# sfp-experimenter.net
KiCad netlist of a schematic drawn in EAGLE
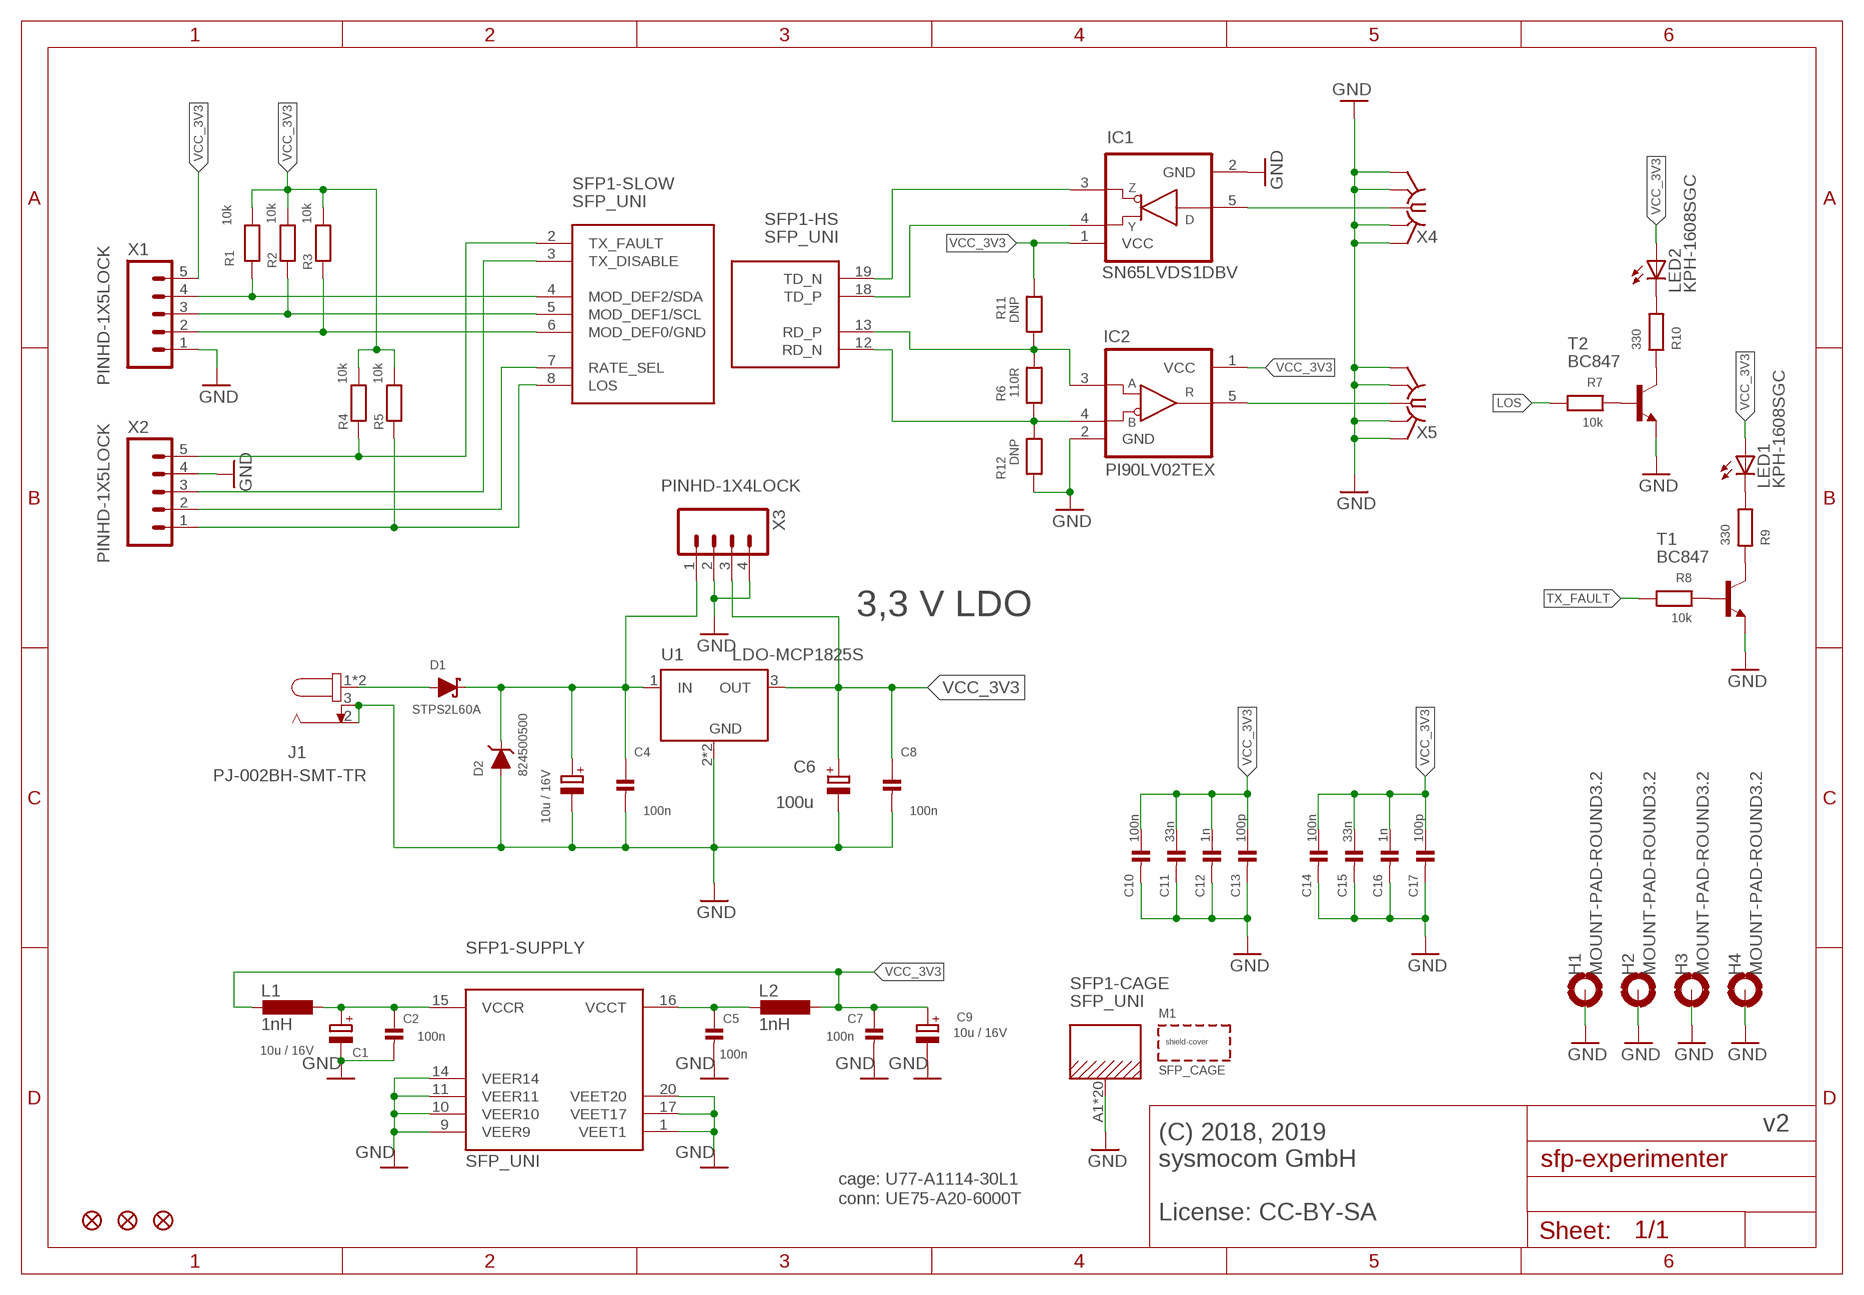
[diagram p0: schematic, sheet 1]

(export (version "E")
  (design (tool "Eeschema 10.0.6"))
  (components
    (comp (ref "C1")
      (value "10u / 16V")
      (footprint "eagle-import:CPOL1206")
      (description "CAP CER 10UF 16V X5R 1206")
      (fields
        (field (name "MANUFACTURER") "Samsung Electro-Mechanics")
        (field (name "MANUFACTURERPARTNUMBER") "CL31A106KOHNNNE")
      )
      (libsource (lib "eagle-import") (part "CPOL-EU-1206"))
    )
    (comp (ref "C2")
      (value "100n")
      (footprint "eagle-import:_0603")
      (description "CAP CER 0.1UF 16V X7R 0603")
      (fields
        (field (name "MANUFACTURER") "Samsung Electro-Mechanics")
        (field (name "MANUFACTURERPARTNUMBER") "CL10B104KO8NNNC")
      )
      (libsource (lib "eagle-import") (part "CAP_CERAMIC_0603"))
    )
    (comp (ref "C3")
      (value "10u / 16V")
      (footprint "eagle-import:CPOL1206")
      (description "CAP CER 10UF 16V X5R 1206")
      (fields
        (field (name "MANUFACTURER") "Samsung Electro-Mechanics")
        (field (name "MANUFACTURERPARTNUMBER") "CL31A106KOHNNNE")
      )
      (libsource (lib "eagle-import") (part "CPOL-EU-1206"))
    )
    (comp (ref "C4")
      (value "100n")
      (footprint "eagle-import:_0603")
      (description "CAP CER 0.1UF 16V X7R 0603")
      (fields
        (field (name "MANUFACTURER") "Samsung Electro-Mechanics")
        (field (name "MANUFACTURERPARTNUMBER") "CL10B104KO8NNNC")
      )
      (libsource (lib "eagle-import") (part "CAP_CERAMIC_0603"))
    )
    (comp (ref "C5")
      (value "100n")
      (footprint "eagle-import:_0603")
      (description "CAP CER 0.1UF 16V X7R 0603")
      (fields
        (field (name "MANUFACTURER") "Samsung Electro-Mechanics")
        (field (name "MANUFACTURERPARTNUMBER") "CL10B104KO8NNNC")
      )
      (libsource (lib "eagle-import") (part "CAP_CERAMIC_0603"))
    )
    (comp (ref "C6")
      (value "100u")
      (footprint "eagle-import:CT6032")
      (description "CAP TANT POLY 100UF 6.3V 2312")
      (fields
        (field (name "MANUFACTURER") "KEMET")
        (field (name "MANUFACTURERPARTNUMBER") "T520C107M006ATE045")
      )
      (libsource (lib "eagle-import") (part "CPOL-EUCT6032"))
    )
    (comp (ref "C7")
      (value "100n")
      (footprint "eagle-import:_0603")
      (description "CAP CER 0.1UF 16V X7R 0603")
      (fields
        (field (name "MANUFACTURER") "Samsung Electro-Mechanics")
        (field (name "MANUFACTURERPARTNUMBER") "CL10B104KO8NNNC")
      )
      (libsource (lib "eagle-import") (part "CAP_CERAMIC_0603"))
    )
    (comp (ref "C8")
      (value "100n")
      (footprint "eagle-import:_0603")
      (description "CAP CER 0.1UF 16V X7R 0603")
      (fields
        (field (name "MANUFACTURER") "Samsung Electro-Mechanics")
        (field (name "MANUFACTURERPARTNUMBER") "CL10B104KO8NNNC")
      )
      (libsource (lib "eagle-import") (part "CAP_CERAMIC_0603"))
    )
    (comp (ref "C9")
      (value "10u / 16V")
      (footprint "eagle-import:CPOL1206")
      (description "CAP CER 10UF 16V X5R 1206")
      (fields
        (field (name "MANUFACTURER") "Samsung Electro-Mechanics")
        (field (name "MANUFACTURERPARTNUMBER") "CL31A106KOHNNNE")
      )
      (libsource (lib "eagle-import") (part "CPOL-EU-1206"))
    )
    (comp (ref "C10")
      (value "100n")
      (footprint "eagle-import:_0603")
      (description "CAP CER 0.1UF 16V X7R 0603")
      (fields
        (field (name "MANUFACTURER") "Samsung Electro-Mechanics")
        (field (name "MANUFACTURERPARTNUMBER") "CL10B104KO8NNNC")
      )
      (libsource (lib "eagle-import") (part "CAP_CERAMIC_0603"))
    )
    (comp (ref "C11")
      (value "33n")
      (footprint "eagle-import:_0603")
      (description "CAP CER 0.033UF 50V X7R 0603")
      (fields
        (field (name "MANUFACTURER") "AVX Corporation")
        (field (name "MANUFACTURERPARTNUMBER") "06035C333JAT2A")
      )
      (libsource (lib "eagle-import") (part "CAP_CERAMIC_0603"))
    )
    (comp (ref "C12")
      (value "1n")
      (footprint "eagle-import:_0603")
      (description "CAP CER 1000PF 50V X7R 0603")
      (fields
        (field (name "MANUFACTURER") "Yageo")
        (field (name "MANUFACTURERPARTNUMBER") "CC0603KRX7R9BB102")
      )
      (libsource (lib "eagle-import") (part "CAP_CERAMIC_0603"))
    )
    (comp (ref "C13")
      (value "100p")
      (footprint "eagle-import:_0603")
      (description "CAP CER 100PF 50V C0G/NPO 0603")
      (fields
        (field (name "MANUFACTURER") "Yageo")
        (field (name "MANUFACTURERPARTNUMBER") "CC0603JRNPO9BN101")
      )
      (libsource (lib "eagle-import") (part "CAP_CERAMIC_0603"))
    )
    (comp (ref "C14")
      (value "100n")
      (footprint "eagle-import:_0603")
      (description "CAP CER 0.1UF 16V X7R 0603")
      (fields
        (field (name "MANUFACTURER") "Samsung Electro-Mechanics")
        (field (name "MANUFACTURERPARTNUMBER") "CL10B104KO8NNNC")
      )
      (libsource (lib "eagle-import") (part "CAP_CERAMIC_0603"))
    )
    (comp (ref "C15")
      (value "33n")
      (footprint "eagle-import:_0603")
      (description "CAP CER 0.033UF 50V X7R 0603")
      (fields
        (field (name "MANUFACTURER") "AVX Corporation")
        (field (name "MANUFACTURERPARTNUMBER") "06035C333JAT2A")
      )
      (libsource (lib "eagle-import") (part "CAP_CERAMIC_0603"))
    )
    (comp (ref "C16")
      (value "1n")
      (footprint "eagle-import:_0603")
      (description "CAP CER 1000PF 50V X7R 0603")
      (fields
        (field (name "MANUFACTURER") "Yageo")
        (field (name "MANUFACTURERPARTNUMBER") "CC0603KRX7R9BB102")
      )
      (libsource (lib "eagle-import") (part "CAP_CERAMIC_0603"))
    )
    (comp (ref "C17")
      (value "100p")
      (footprint "eagle-import:_0603")
      (description "CAP CER 100PF 50V C0G/NPO 0603")
      (fields
        (field (name "MANUFACTURER") "Yageo")
        (field (name "MANUFACTURERPARTNUMBER") "CC0603JRNPO9BN101")
      )
      (libsource (lib "eagle-import") (part "CAP_CERAMIC_0603"))
    )
    (comp (ref "D1")
      (value "STPS2L60A")
      (footprint "eagle-import:SMADIODE")
      (description "DIODE SCHOTTKY 60V 2A SMA")
      (fields (field (name "MANUFACTURER") "STMicroelectronics"))
      (libsource (lib "eagle-import") (part "DIODE-SCHOTTKY-SMA"))
    )
    (comp (ref "D2")
      (value "824500500")
      (footprint "eagle-import:SMADIODE")
      (description "TVS DIODE 5VWM 9.2VC SMA")
      (fields (field (name "MANUFACTURER") "Bourns Inc.") (field (name "MANUFACTURERPARTNUMBER") "SMAJ5.0A"))
      (libsource (lib "eagle-import") (part "DIODE-TVS-SMA"))
    )
    (comp (ref "FID1")
      (value "FIDUCIAL1X2.5")
      (footprint "eagle-import:FIDUCIAL-1X2.5")
      (libsource (lib "eagle-import") (part "FIDUCIAL1X2.5"))
    )
    (comp (ref "FID2")
      (value "FIDUCIAL1X2.5")
      (footprint "eagle-import:FIDUCIAL-1X2.5")
      (libsource (lib "eagle-import") (part "FIDUCIAL1X2.5"))
    )
    (comp (ref "FID3")
      (value "FIDUCIAL1X2.5")
      (footprint "eagle-import:FIDUCIAL-1X2.5")
      (libsource (lib "eagle-import") (part "FIDUCIAL1X2.5"))
    )
    (comp (ref "H1")
      (value "MOUNT-PAD-ROUND3.2")
      (footprint "eagle-import:3,2-PAD")
      (description "NO DESCRIPTION")
      (fields
        (field (name "MANUFACTURER") "UNKNOWN MANUFACTURER")
        (field (name "MANUFACTURERPARTNUMBER") "UNKNOWN MANUFACTURER PART NUMBER")
      )
      (libsource (lib "eagle-import") (part "MOUNT-PAD-ROUND3.2"))
    )
    (comp (ref "H2")
      (value "MOUNT-PAD-ROUND3.2")
      (footprint "eagle-import:3,2-PAD")
      (description "NO DESCRIPTION")
      (fields
        (field (name "MANUFACTURER") "UNKNOWN MANUFACTURER")
        (field (name "MANUFACTURERPARTNUMBER") "UNKNOWN MANUFACTURER PART NUMBER")
      )
      (libsource (lib "eagle-import") (part "MOUNT-PAD-ROUND3.2"))
    )
    (comp (ref "H3")
      (value "MOUNT-PAD-ROUND3.2")
      (footprint "eagle-import:3,2-PAD")
      (description "NO DESCRIPTION")
      (fields
        (field (name "MANUFACTURER") "UNKNOWN MANUFACTURER")
        (field (name "MANUFACTURERPARTNUMBER") "UNKNOWN MANUFACTURER PART NUMBER")
      )
      (libsource (lib "eagle-import") (part "MOUNT-PAD-ROUND3.2"))
    )
    (comp (ref "H4")
      (value "MOUNT-PAD-ROUND3.2")
      (footprint "eagle-import:3,2-PAD")
      (description "NO DESCRIPTION")
      (fields
        (field (name "MANUFACTURER") "UNKNOWN MANUFACTURER")
        (field (name "MANUFACTURERPARTNUMBER") "UNKNOWN MANUFACTURER PART NUMBER")
      )
      (libsource (lib "eagle-import") (part "MOUNT-PAD-ROUND3.2"))
    )
    (comp (ref "IC1")
      (value "SN65LVDS1DBV")
      (footprint "eagle-import:SOT23-5")
      (description "IC DRIVER 1/0 SOT23-5")
      (fields
        (field (name "MANUFACTURER") "Texas Instruments")
        (field (name "MANUFACTURERPARTNUMBER") "SN65LVDS1DBVR")
      )
      (libsource (lib "eagle-import") (part "SN65LVDS1DBV"))
    )
    (comp (ref "IC2")
      (value "PI90LV02TEX")
      (footprint "eagle-import:SOT23-5")
      (description "IC RECEIVER 0/1 SOT23-5")
      (fields (field (name "MANUFACTURER") "Diodes Incorporated"))
      (libsource (lib "eagle-import") (part "SN65LVDT2DBV"))
    )
    (comp (ref "J1")
      (value "PJ-002BH-SMT-TR")
      (footprint "eagle-import:694108106102")
      (description "CONN PWR JACK 2.5X5.5MM SOLDER")
      (fields (field (name "MANUFACTURER") "CUI Devices"))
      (libsource (lib "eagle-import") (part "694108106102"))
    )
    (comp (ref "L1")
      (value "1nH")
      (footprint "eagle-import:0603")
      (description "FIXED IND 1NH 500MA 50 MOHM SMD")
      (fields
        (field (name "MANUFACTURER") "Abracon LLC")
        (field (name "MANUFACTURERPARTNUMBER") "AIMC-0603-1N0S-T")
      )
      (libsource (lib "eagle-import") (part "L-EU_0603"))
    )
    (comp (ref "L2")
      (value "1nH")
      (footprint "eagle-import:0603")
      (description "FIXED IND 1NH 500MA 50 MOHM SMD")
      (fields
        (field (name "MANUFACTURER") "Abracon LLC")
        (field (name "MANUFACTURERPARTNUMBER") "AIMC-0603-1N0S-T")
      )
      (libsource (lib "eagle-import") (part "L-EU_0603"))
    )
    (comp (ref "LED1")
      (value "KPH-1608SGC")
      (footprint "eagle-import:CHIP-LED0603")
      (description "NO DESCRIPTION")
      (fields
        (field (name "MANUFACTURER") "UNKNOWN MANUFACTURER")
        (field (name "MANUFACTURERPARTNUMBER") "UNKNOWN MANUFACTURER PART NUMBER")
      )
      (libsource (lib "eagle-import") (part "LEDCHIP-LED0603"))
    )
    (comp (ref "LED2")
      (value "KPH-1608SGC")
      (footprint "eagle-import:CHIP-LED0603")
      (description "NO DESCRIPTION")
      (fields
        (field (name "MANUFACTURER") "UNKNOWN MANUFACTURER")
        (field (name "MANUFACTURERPARTNUMBER") "UNKNOWN MANUFACTURER PART NUMBER")
      )
      (libsource (lib "eagle-import") (part "LEDCHIP-LED0603"))
    )
    (comp (ref "R1")
      (value "10k")
      (footprint "eagle-import:_0603")
      (description "RES 10K OHM 1% 1/10W 0603")
      (fields (field (name "MANUFACTURER") "YAGEO") (field (name "MANUFACTURERPARTNUMBER") "RC0603FR-0710KL"))
      (libsource (lib "eagle-import") (part "sfp-experimenter_RESISTOR_0603"))
    )
    (comp (ref "R2")
      (value "10k")
      (footprint "eagle-import:_0603")
      (description "RES 10K OHM 1% 1/10W 0603")
      (fields (field (name "MANUFACTURER") "YAGEO") (field (name "MANUFACTURERPARTNUMBER") "RC0603FR-0710KL"))
      (libsource (lib "eagle-import") (part "sfp-experimenter_RESISTOR_0603"))
    )
    (comp (ref "R3")
      (value "10k")
      (footprint "eagle-import:_0603")
      (description "RES 10K OHM 1% 1/10W 0603")
      (fields (field (name "MANUFACTURER") "YAGEO") (field (name "MANUFACTURERPARTNUMBER") "RC0603FR-0710KL"))
      (libsource (lib "eagle-import") (part "sfp-experimenter_RESISTOR_0603"))
    )
    (comp (ref "R4")
      (value "10k")
      (footprint "eagle-import:_0603")
      (description "RES 10K OHM 1% 1/10W 0603")
      (fields (field (name "MANUFACTURER") "YAGEO") (field (name "MANUFACTURERPARTNUMBER") "RC0603FR-0710KL"))
      (libsource (lib "eagle-import") (part "sfp-experimenter_RESISTOR_0603"))
    )
    (comp (ref "R5")
      (value "10k")
      (footprint "eagle-import:_0603")
      (description "RES 10K OHM 1% 1/10W 0603")
      (fields (field (name "MANUFACTURER") "YAGEO") (field (name "MANUFACTURERPARTNUMBER") "RC0603FR-0710KL"))
      (libsource (lib "eagle-import") (part "sfp-experimenter_RESISTOR_0603"))
    )
    (comp (ref "R6")
      (value "110R")
      (footprint "eagle-import:_0402")
      (description "RES 110 OHM 1% 1/10W 0603")
      (fields
        (field (name "MANUFACTURER") "YAGEO")
        (field (name "MANUFACTURERPARTNUMBER") "RC0603FR-13110RL")
      )
      (libsource (lib "eagle-import") (part "sfp-experimenter_RESISTOR_0402"))
    )
    (comp (ref "R7")
      (value "10k")
      (footprint "eagle-import:_0603")
      (description "RES 10K OHM 1% 1/10W 0603")
      (fields (field (name "MANUFACTURER") "YAGEO") (field (name "MANUFACTURERPARTNUMBER") "RC0603FR-0710KL"))
      (libsource (lib "eagle-import") (part "RESISTOR_0603"))
    )
    (comp (ref "R8")
      (value "10k")
      (footprint "eagle-import:_0603")
      (description "RES 10K OHM 1% 1/10W 0603")
      (fields (field (name "MANUFACTURER") "YAGEO") (field (name "MANUFACTURERPARTNUMBER") "RC0603FR-0710KL"))
      (libsource (lib "eagle-import") (part "RESISTOR_0603"))
    )
    (comp (ref "R9")
      (value "330")
      (footprint "eagle-import:_0603")
      (description "RES SMD 330 OHM 5% 1/10W 0603")
      (fields
        (field (name "MANUFACTURER") "Panasonic Electronic Components")
        (field (name "MANUFACTURERPARTNUMBER") "ERJ-3GEYJ331V")
      )
      (libsource (lib "eagle-import") (part "RESISTOR_0603"))
    )
    (comp (ref "R10")
      (value "330")
      (footprint "eagle-import:_0603")
      (description "RES SMD 330 OHM 5% 1/10W 0603")
      (fields
        (field (name "MANUFACTURER") "Panasonic Electronic Components")
        (field (name "MANUFACTURERPARTNUMBER") "ERJ-3GEYJ331V")
      )
      (libsource (lib "eagle-import") (part "RESISTOR_0603"))
    )
    (comp (ref "R11")
      (value "DNP")
      (footprint "eagle-import:_0603")
      (description "NO DESCRIPTION")
      (fields
        (field (name "MANUFACTURER") "UNKNOWN MANUFACTURER")
        (field (name "MANUFACTURERPARTNUMBER") "UNKNOWN MANUFACTURER PART NUMBER")
      )
      (libsource (lib "eagle-import") (part "sfp-experimenter_RESISTOR_0603"))
    )
    (comp (ref "R12")
      (value "DNP")
      (footprint "eagle-import:_0603")
      (description "RES 100K OHM 1% 1/10W 0603")
      (fields
        (field (name "MANUFACTURER") "KOA Speer Electronics, Inc.")
        (field (name "MANUFACTURERPARTNUMBER") "RK73H1JTTD1003F")
      )
      (libsource (lib "eagle-import") (part "RESISTOR_0603"))
    )
    (comp (ref "SFP1")
      (value "SFP_UNI")
      (footprint "eagle-import:SFP_COMBINED")
      (description "CONN SFP RCPT 20POS SLD R/A SMD")
      (fields
        (field (name "CLASS") "SFP")
        (field (name "LINK") "https://www.digikey.com/product-detail/en/amphenol-icc-commercial-products/UE75-A20-6000T/UE75-A20-6000TCT-ND/1242798")
        (field (name "MANUFACTURER") "Amphenol ICC (Commercial Products)")
        (field (name "MANUFACTURERPARTNUMBER") "UE75-A20-6000T")
        (field (name "POPULATED") "TRUE")
        (field (name "ROHSCERTIFICATE") "RoHS Compliant")
        (field (name "SOURCE") "DIGIKEY")
        (field (name "SOURCEPARTNUMBER") "UE75-A20-6000TCT-ND")
      )
      (libsource (lib "eagle-import") (part "SFP_UNI"))
    )
    (comp (ref "T1")
      (value "BC847")
      (footprint "eagle-import:SOT23-BEC")
      (description "TRANS NPN GP 100MA 45V SOT23")
      (fields
        (field (name "MANUFACTURER") "NXP Semiconductors")
        (field (name "MANUFACTURERPARTNUMBER") "BC847C,215")
      )
      (libsource (lib "eagle-import") (part "-NPN-SOT23-BECBC847C"))
    )
    (comp (ref "T2")
      (value "BC847")
      (footprint "eagle-import:SOT23-BEC")
      (description "TRANS NPN GP 100MA 45V SOT23")
      (fields
        (field (name "MANUFACTURER") "NXP Semiconductors")
        (field (name "MANUFACTURERPARTNUMBER") "BC847C,215")
      )
      (libsource (lib "eagle-import") (part "-NPN-SOT23-BECBC847C"))
    )
    (comp (ref "U1")
      (value "LDO-MCP1825S")
      (footprint "eagle-import:SOT223")
      (description "IC REG LIN 3.3V 500MA SOT223-3")
      (fields
        (field (name "MANUFACTURER") "Microchip Technology")
        (field (name "MANUFACTURERPARTNUMBER") "MCP1825ST-3302E/DB")
      )
      (libsource (lib "eagle-import") (part "LDO-MCP1825S"))
    )
    (comp (ref "X1")
      (value "PINHD-1X5LOCK")
      (footprint "eagle-import:1X05_LOCK")
      (description "NO DESCRIPTION")
      (fields
        (field (name "MANUFACTURER") "UNKNOWN MANUFACTURER")
        (field (name "MANUFACTURERPARTNUMBER") "UNKNOWN MANUFACTURER PART NUMBER")
      )
      (libsource (lib "eagle-import") (part "PINHD-1X5LOCK"))
    )
    (comp (ref "X2")
      (value "PINHD-1X5LOCK")
      (footprint "eagle-import:1X05_LOCK")
      (description "NO DESCRIPTION")
      (fields
        (field (name "MANUFACTURER") "UNKNOWN MANUFACTURER")
        (field (name "MANUFACTURERPARTNUMBER") "UNKNOWN MANUFACTURER PART NUMBER")
      )
      (libsource (lib "eagle-import") (part "PINHD-1X5LOCK"))
    )
    (comp (ref "X3")
      (value "PINHD-1X4LOCK")
      (footprint "eagle-import:1X04_LOCK")
      (description "NO DESCRIPTION")
      (fields
        (field (name "MANUFACTURER") "UNKNOWN MANUFACTURER")
        (field (name "MANUFACTURERPARTNUMBER") "UNKNOWN MANUFACTURER PART NUMBER")
      )
      (libsource (lib "eagle-import") (part "PINHD-1X4LOCK"))
    )
    (comp (ref "X4")
      (value "SMA-F-S-EDGE")
      (footprint "eagle-import:SMA-F-S-EDGE")
      (description "NO DESCRIPTION")
      (fields
        (field (name "MANUFACTURER") "UNKNOWN MANUFACTURER")
        (field (name "MANUFACTURERPARTNUMBER") "UNKNOWN MANUFACTURER PART NUMBER")
      )
      (libsource (lib "eagle-import") (part "SMA-F-S-EDGE"))
    )
    (comp (ref "X5")
      (value "SMA-F-S-EDGE")
      (footprint "eagle-import:SMA-F-S-EDGE")
      (description "NO DESCRIPTION")
      (fields
        (field (name "MANUFACTURER") "UNKNOWN MANUFACTURER")
        (field (name "MANUFACTURERPARTNUMBER") "UNKNOWN MANUFACTURER PART NUMBER")
      )
      (libsource (lib "eagle-import") (part "SMA-F-S-EDGE"))
    )
  )
  (nets
    (net (code "1") (name "GND") (class "Default")
      (node (ref "C1") (pin "-") (pinfunction "-_-") (pintype "passive"))
      (node (ref "C10") (pin "2") (pinfunction "2_2") (pintype "passive"))
      (node (ref "C11") (pin "2") (pinfunction "2_2") (pintype "passive"))
      (node (ref "C12") (pin "2") (pinfunction "2_2") (pintype "passive"))
      (node (ref "C13") (pin "2") (pinfunction "2_2") (pintype "passive"))
      (node (ref "C14") (pin "2") (pinfunction "2_2") (pintype "passive"))
      (node (ref "C15") (pin "2") (pinfunction "2_2") (pintype "passive"))
      (node (ref "C16") (pin "2") (pinfunction "2_2") (pintype "passive"))
      (node (ref "C17") (pin "2") (pinfunction "2_2") (pintype "passive"))
      (node (ref "C2") (pin "2") (pinfunction "2_2") (pintype "passive"))
      (node (ref "C3") (pin "-") (pinfunction "-_-") (pintype "passive"))
      (node (ref "C4") (pin "2") (pinfunction "2_2") (pintype "passive"))
      (node (ref "C5") (pin "2") (pinfunction "2_2") (pintype "passive"))
      (node (ref "C6") (pin "-") (pinfunction "-_-") (pintype "passive"))
      (node (ref "C7") (pin "2") (pinfunction "2_2") (pintype "passive"))
      (node (ref "C8") (pin "2") (pinfunction "2_2") (pintype "passive"))
      (node (ref "C9") (pin "-") (pinfunction "-_-") (pintype "passive"))
      (node (ref "D2") (pin "A") (pinfunction "A_A") (pintype "passive"))
      (node (ref "H1") (pin "B3,2") (pinfunction "MOUNT_B3,2") (pintype "passive"))
      (node (ref "H2") (pin "B3,2") (pinfunction "MOUNT_B3,2") (pintype "passive"))
      (node (ref "H3") (pin "B3,2") (pinfunction "MOUNT_B3,2") (pintype "passive"))
      (node (ref "H4") (pin "B3,2") (pinfunction "MOUNT_B3,2") (pintype "passive"))
      (node (ref "IC1") (pin "2") (pinfunction "GND_2") (pintype "power_in"))
      (node (ref "IC2") (pin "2") (pinfunction "GND_2") (pintype "power_in"))
      (node (ref "J1") (pin "2") (pinfunction "2_2") (pintype "passive"))
      (node (ref "J1") (pin "3") (pinfunction "3_3") (pintype "passive"))
      (node (ref "R12") (pin "2") (pinfunction "2_2") (pintype "passive"))
      (node (ref "SFP1") (pin "1") (pinfunction "VEET1_1") (pintype "power_in"))
      (node (ref "SFP1") (pin "10") (pinfunction "VEER10_10") (pintype "power_in"))
      (node (ref "SFP1") (pin "11") (pinfunction "VEER11_11") (pintype "power_in"))
      (node (ref "SFP1") (pin "14") (pinfunction "VEER14_14") (pintype "power_in"))
      (node (ref "SFP1") (pin "17") (pinfunction "VEET17_17") (pintype "power_in"))
      (node (ref "SFP1") (pin "20") (pinfunction "VEET20_20") (pintype "power_in"))
      (node (ref "SFP1") (pin "9") (pinfunction "VEER9_9") (pintype "power_in"))
      (node (ref "SFP1") (pin "A1") (pinfunction "CAGE_A1") (pintype "power_in"))
      (node (ref "SFP1") (pin "A10") (pinfunction "CAGE_A10") (pintype "power_in"))
      (node (ref "SFP1") (pin "A11") (pinfunction "CAGE_A11") (pintype "power_in"))
      (node (ref "SFP1") (pin "A12") (pinfunction "CAGE_A12") (pintype "power_in"))
      (node (ref "SFP1") (pin "A2") (pinfunction "CAGE_A2") (pintype "power_in"))
      (node (ref "SFP1") (pin "A3") (pinfunction "CAGE_A3") (pintype "power_in"))
      (node (ref "SFP1") (pin "A4") (pinfunction "CAGE_A4") (pintype "power_in"))
      (node (ref "SFP1") (pin "A5") (pinfunction "CAGE_A5") (pintype "power_in"))
      (node (ref "SFP1") (pin "A6") (pinfunction "CAGE_A6") (pintype "power_in"))
      (node (ref "SFP1") (pin "A7") (pinfunction "CAGE_A7") (pintype "power_in"))
      (node (ref "SFP1") (pin "A8") (pinfunction "CAGE_A8") (pintype "power_in"))
      (node (ref "SFP1") (pin "B1") (pinfunction "CAGE_B1") (pintype "power_in"))
      (node (ref "SFP1") (pin "B10") (pinfunction "CAGE_B10") (pintype "power_in"))
      (node (ref "SFP1") (pin "B2") (pinfunction "CAGE_B2") (pintype "power_in"))
      (node (ref "SFP1") (pin "B3") (pinfunction "CAGE_B3") (pintype "power_in"))
      (node (ref "SFP1") (pin "B4") (pinfunction "CAGE_B4") (pintype "power_in"))
      (node (ref "SFP1") (pin "B5") (pinfunction "CAGE_B5") (pintype "power_in"))
      (node (ref "SFP1") (pin "B6") (pinfunction "CAGE_B6") (pintype "power_in"))
      (node (ref "SFP1") (pin "B7") (pinfunction "CAGE_B7") (pintype "power_in"))
      (node (ref "SFP1") (pin "B8") (pinfunction "CAGE_B8") (pintype "power_in"))
      (node (ref "T1") (pin "E") (pinfunction "E_E") (pintype "passive"))
      (node (ref "T2") (pin "E") (pinfunction "E_E") (pintype "passive"))
      (node (ref "U1") (pin "2") (pinfunction "GND_2") (pintype "power_in"))
      (node (ref "U1") (pin "4") (pinfunction "GND_4") (pintype "power_in"))
      (node (ref "X1") (pin "1") (pinfunction "1_1") (pintype "passive"))
      (node (ref "X2") (pin "4") (pinfunction "4_4") (pintype "passive"))
      (node (ref "X3") (pin "2") (pinfunction "2_2") (pintype "passive"))
      (node (ref "X3") (pin "4") (pinfunction "4_4") (pintype "passive"))
      (node (ref "X4") (pin "BG1") (pinfunction "GND_BG1") (pintype "power_in"))
      (node (ref "X4") (pin "BG2") (pinfunction "GND_BG2") (pintype "power_in"))
      (node (ref "X4") (pin "TG1") (pinfunction "GND_TG1") (pintype "power_in"))
      (node (ref "X4") (pin "TG2") (pinfunction "GND_TG2") (pintype "power_in"))
      (node (ref "X5") (pin "BG1") (pinfunction "GND_BG1") (pintype "power_in"))
      (node (ref "X5") (pin "BG2") (pinfunction "GND_BG2") (pintype "power_in"))
      (node (ref "X5") (pin "TG1") (pinfunction "GND_TG1") (pintype "power_in"))
      (node (ref "X5") (pin "TG2") (pinfunction "GND_TG2") (pintype "power_in"))
    )
    (net (code "2") (name "LOS") (class "Default")
      (node (ref "R5") (pin "1") (pinfunction "1_1") (pintype "passive"))
      (node (ref "R7") (pin "2") (pinfunction "2_2") (pintype "passive"))
      (node (ref "SFP1") (pin "8") (pinfunction "LOS_8") (pintype "output"))
      (node (ref "X2") (pin "1") (pinfunction "1_1") (pintype "passive"))
    )
    (net (code "3") (name "Net-(D1-PadA)") (class "Default")
      (node (ref "D1") (pin "A") (pinfunction "A_A") (pintype "passive"))
      (node (ref "J1") (pin "1") (pinfunction "1_1") (pintype "passive"))
      (node (ref "J1") (pin "1-1") (pinfunction "1_1-1") (pintype "passive"))
    )
    (net (code "4") (name "Net-(IC1-D)") (class "Default")
      (node (ref "IC1") (pin "5") (pinfunction "D_5") (pintype "input"))
      (node (ref "X4") (pin "C") (pinfunction "1_C") (pintype "passive"))
    )
    (net (code "5") (name "Net-(IC1-Y)") (class "Default")
      (node (ref "IC1") (pin "4") (pinfunction "Y_4") (pintype "output"))
      (node (ref "SFP1") (pin "18") (pinfunction "TD_P_18") (pintype "input"))
    )
    (net (code "6") (name "Net-(IC1-Z)") (class "Default")
      (node (ref "IC1") (pin "3") (pinfunction "Z_3") (pintype "output"))
      (node (ref "SFP1") (pin "19") (pinfunction "TD_N_19") (pintype "input"))
    )
    (net (code "7") (name "Net-(IC2-A)") (class "Default")
      (node (ref "IC2") (pin "3") (pinfunction "A_3") (pintype "input"))
      (node (ref "R11") (pin "2") (pinfunction "2_2") (pintype "passive"))
      (node (ref "R6") (pin "1") (pinfunction "1_1") (pintype "passive"))
      (node (ref "SFP1") (pin "13") (pinfunction "RD_P_13") (pintype "output"))
    )
    (net (code "8") (name "Net-(IC2-B)") (class "Default")
      (node (ref "IC2") (pin "4") (pinfunction "B_4") (pintype "input"))
      (node (ref "R12") (pin "1") (pinfunction "1_1") (pintype "passive"))
      (node (ref "R6") (pin "2") (pinfunction "2_2") (pintype "passive"))
      (node (ref "SFP1") (pin "12") (pinfunction "RD_N_12") (pintype "output"))
    )
    (net (code "9") (name "Net-(IC2-R)") (class "Default")
      (node (ref "IC2") (pin "5") (pinfunction "R_5") (pintype "output"))
      (node (ref "X5") (pin "C") (pinfunction "1_C") (pintype "passive"))
    )
    (net (code "10") (name "Net-(LED1-PadC)") (class "Default")
      (node (ref "LED1") (pin "C") (pinfunction "C_C") (pintype "passive"))
      (node (ref "R9") (pin "2") (pinfunction "2_2") (pintype "passive"))
    )
    (net (code "11") (name "Net-(LED2-PadC)") (class "Default")
      (node (ref "LED2") (pin "C") (pinfunction "C_C") (pintype "passive"))
      (node (ref "R10") (pin "2") (pinfunction "2_2") (pintype "passive"))
    )
    (net (code "12") (name "Net-(R7-Pad1)") (class "Default")
      (node (ref "R7") (pin "1") (pinfunction "1_1") (pintype "passive"))
      (node (ref "T2") (pin "B") (pinfunction "B_B") (pintype "passive"))
    )
    (net (code "13") (name "Net-(R8-Pad1)") (class "Default")
      (node (ref "R8") (pin "1") (pinfunction "1_1") (pintype "passive"))
      (node (ref "T1") (pin "B") (pinfunction "B_B") (pintype "passive"))
    )
    (net (code "14") (name "Net-(R9-Pad1)") (class "Default")
      (node (ref "R9") (pin "1") (pinfunction "1_1") (pintype "passive"))
      (node (ref "T1") (pin "C") (pinfunction "C_C") (pintype "passive"))
    )
    (net (code "15") (name "Net-(R10-Pad1)") (class "Default")
      (node (ref "R10") (pin "1") (pinfunction "1_1") (pintype "passive"))
      (node (ref "T2") (pin "C") (pinfunction "C_C") (pintype "passive"))
    )
    (net (code "16") (name "Net-(SFP1C-MOD_DEF0{slash}GND)") (class "Default")
      (node (ref "R3") (pin "1") (pinfunction "1_1") (pintype "passive"))
      (node (ref "SFP1") (pin "6") (pinfunction "MOD_DEF0/GND_6") (pintype "passive"))
      (node (ref "X1") (pin "2") (pinfunction "2_2") (pintype "passive"))
    )
    (net (code "17") (name "Net-(SFP1C-MOD_DEF1{slash}SCL)") (class "Default")
      (node (ref "R2") (pin "1") (pinfunction "1_1") (pintype "passive"))
      (node (ref "SFP1") (pin "5") (pinfunction "MOD_DEF1/SCL_5") (pintype "bidirectional"))
      (node (ref "X1") (pin "3") (pinfunction "3_3") (pintype "passive"))
    )
    (net (code "18") (name "Net-(SFP1C-MOD_DEF2{slash}SDA)") (class "Default")
      (node (ref "R1") (pin "1") (pinfunction "1_1") (pintype "passive"))
      (node (ref "SFP1") (pin "4") (pinfunction "MOD_DEF2/SDA_4") (pintype "bidirectional"))
      (node (ref "X1") (pin "4") (pinfunction "4_4") (pintype "passive"))
    )
    (net (code "19") (name "Net-(SFP1C-RATE_SEL)") (class "Default")
      (node (ref "SFP1") (pin "7") (pinfunction "RATE_SEL_7") (pintype "input"))
      (node (ref "X2") (pin "2") (pinfunction "2_2") (pintype "passive"))
    )
    (net (code "20") (name "Net-(SFP1C-TX_DISABLE)") (class "Default")
      (node (ref "SFP1") (pin "3") (pinfunction "TX_DISABLE_3") (pintype "input"))
      (node (ref "X2") (pin "3") (pinfunction "3_3") (pintype "passive"))
    )
    (net (code "21") (name "Net-(SFP1D-VCCR)") (class "Default")
      (node (ref "C1") (pin "+") (pinfunction "+_+") (pintype "passive"))
      (node (ref "C2") (pin "1") (pinfunction "1_1") (pintype "passive"))
      (node (ref "L1") (pin "1") (pinfunction "1_1") (pintype "passive"))
      (node (ref "SFP1") (pin "15") (pinfunction "VCCR_15") (pintype "power_in"))
    )
    (net (code "22") (name "Net-(SFP1D-VCCT)") (class "Default")
      (node (ref "C5") (pin "1") (pinfunction "1_1") (pintype "passive"))
      (node (ref "L2") (pin "2") (pinfunction "2_2") (pintype "passive"))
      (node (ref "SFP1") (pin "16") (pinfunction "VCCT_16") (pintype "power_in"))
    )
    (net (code "23") (name "Net-(U1-IN)") (class "Default")
      (node (ref "C3") (pin "+") (pinfunction "+_+") (pintype "passive"))
      (node (ref "C4") (pin "1") (pinfunction "1_1") (pintype "passive"))
      (node (ref "D1") (pin "C") (pinfunction "C_C") (pintype "passive"))
      (node (ref "D2") (pin "C") (pinfunction "C_C") (pintype "passive"))
      (node (ref "U1") (pin "1") (pinfunction "IN_1") (pintype "input"))
      (node (ref "X3") (pin "1") (pinfunction "1_1") (pintype "passive"))
    )
    (net (code "24") (name "TX_FAULT") (class "Default")
      (node (ref "R4") (pin "1") (pinfunction "1_1") (pintype "passive"))
      (node (ref "R8") (pin "2") (pinfunction "2_2") (pintype "passive"))
      (node (ref "SFP1") (pin "2") (pinfunction "TX_FAULT_2") (pintype "output"))
      (node (ref "X2") (pin "5") (pinfunction "5_5") (pintype "passive"))
    )
    (net (code "25") (name "VCC_3V3") (class "Default")
      (node (ref "C10") (pin "1") (pinfunction "1_1") (pintype "passive"))
      (node (ref "C11") (pin "1") (pinfunction "1_1") (pintype "passive"))
      (node (ref "C12") (pin "1") (pinfunction "1_1") (pintype "passive"))
      (node (ref "C13") (pin "1") (pinfunction "1_1") (pintype "passive"))
      (node (ref "C14") (pin "1") (pinfunction "1_1") (pintype "passive"))
      (node (ref "C15") (pin "1") (pinfunction "1_1") (pintype "passive"))
      (node (ref "C16") (pin "1") (pinfunction "1_1") (pintype "passive"))
      (node (ref "C17") (pin "1") (pinfunction "1_1") (pintype "passive"))
      (node (ref "C6") (pin "+") (pinfunction "+_+") (pintype "passive"))
      (node (ref "C7") (pin "1") (pinfunction "1_1") (pintype "passive"))
      (node (ref "C8") (pin "1") (pinfunction "1_1") (pintype "passive"))
      (node (ref "C9") (pin "+") (pinfunction "+_+") (pintype "passive"))
      (node (ref "IC1") (pin "1") (pinfunction "VCC_1") (pintype "power_in"))
      (node (ref "IC2") (pin "1") (pinfunction "VCC_1") (pintype "power_in"))
      (node (ref "L1") (pin "2") (pinfunction "2_2") (pintype "passive"))
      (node (ref "L2") (pin "1") (pinfunction "1_1") (pintype "passive"))
      (node (ref "LED1") (pin "A") (pinfunction "A_A") (pintype "passive"))
      (node (ref "LED2") (pin "A") (pinfunction "A_A") (pintype "passive"))
      (node (ref "R1") (pin "2") (pinfunction "2_2") (pintype "passive"))
      (node (ref "R11") (pin "1") (pinfunction "1_1") (pintype "passive"))
      (node (ref "R2") (pin "2") (pinfunction "2_2") (pintype "passive"))
      (node (ref "R3") (pin "2") (pinfunction "2_2") (pintype "passive"))
      (node (ref "R4") (pin "2") (pinfunction "2_2") (pintype "passive"))
      (node (ref "R5") (pin "2") (pinfunction "2_2") (pintype "passive"))
      (node (ref "U1") (pin "3") (pinfunction "OUT_3") (pintype "passive"))
      (node (ref "X1") (pin "5") (pinfunction "5_5") (pintype "passive"))
      (node (ref "X3") (pin "3") (pinfunction "3_3") (pintype "passive"))
    )
  )
)
